# sch.net
KiCad netlist of a schematic drawn in Altium Designer
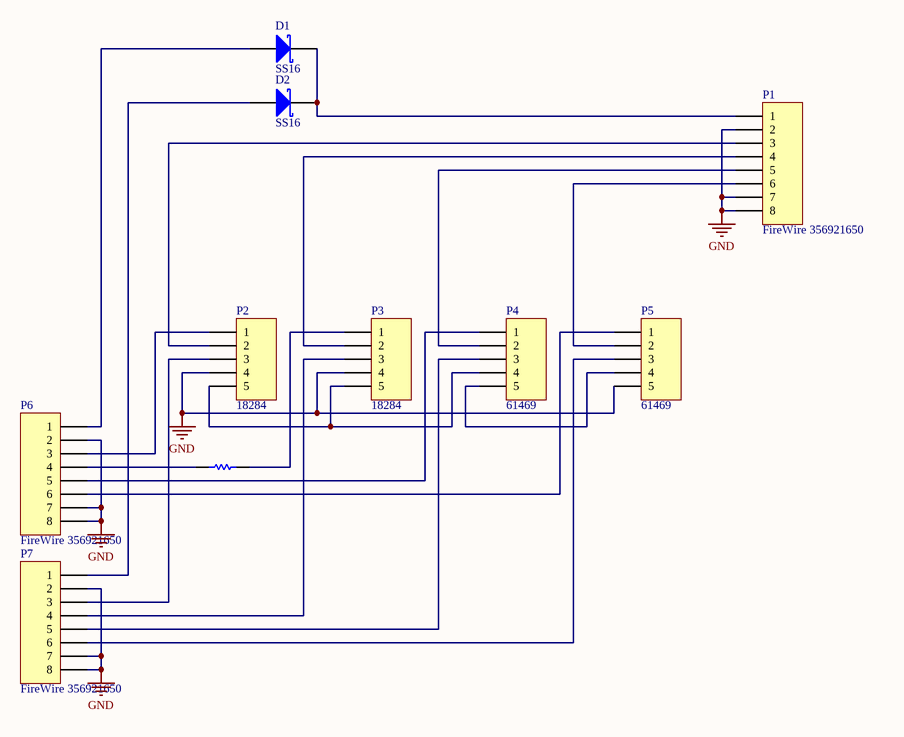
[diagram p0: sch.SchDoc]

(export (version "E")
  (design (tool "Eeschema 10.0.6"))
  (components
    (comp (ref "D1")
      (value "SS16")
      (footprint "RR_SMB")
      (description "DIODE SCHOTTKY 60V 1A SMA")
      (fields (field (name "MANUFACTURER") "FairchildSemiconductor"))
      (libsource (lib "RozumLibrary") (part "SS16"))
    )
    (comp (ref "D2")
      (value "SS16")
      (footprint "RR_SMB")
      (description "DIODE SCHOTTKY 60V 1A SMA")
      (fields (field (name "MANUFACTURER") "FairchildSemiconductor"))
      (libsource (lib "RozumLibrary") (part "SS16"))
    )
    (comp (ref "P1")
      (value "FireWire 356921650")
      (footprint "DS1102")
      (description "IEEE 1394 (DS1102), SMD розетка на плату (OBSOLETE)")
      (fields (field (name "PUBLISHER") "Altium Limited"))
      (libsource (lib "") (part "Header 8_1"))
    )
    (comp (ref "P2")
      (value "18284")
      (footprint "RES55A")
      (description "Header, 5-Pin")
      (fields (field (name "PUBLISHER") "Altium Limited"))
      (libsource (lib "Miscellaneous Connectors") (part "Header 5"))
    )
    (comp (ref "P3")
      (value "18284")
      (footprint "RES55A")
      (description "Header, 5-Pin")
      (fields (field (name "PUBLISHER") "Altium Limited"))
      (libsource (lib "Miscellaneous Connectors") (part "Header 5"))
    )
    (comp (ref "P4")
      (value "61469")
      (footprint "RES55A")
      (description "Header, 5-Pin")
      (fields (field (name "PUBLISHER") "Altium Limited"))
      (libsource (lib "Miscellaneous Connectors") (part "Header 5"))
    )
    (comp (ref "P5")
      (value "61469")
      (footprint "RES55A")
      (description "Header, 5-Pin")
      (fields (field (name "PUBLISHER") "Altium Limited"))
      (libsource (lib "Miscellaneous Connectors") (part "Header 5"))
    )
    (comp (ref "P6")
      (value "FireWire 356921650")
      (footprint "DS1102")
      (description "IEEE 1394 (DS1102), SMD розетка на плату (OBSOLETE)")
      (fields (field (name "PUBLISHER") "Altium Limited"))
      (libsource (lib "Miscellaneous Connectors") (part "Header 8"))
    )
    (comp (ref "P7")
      (value "FireWire 356921650")
      (footprint "DS1102")
      (description "IEEE 1394 (DS1102), SMD розетка на плату (OBSOLETE)")
      (fields (field (name "PUBLISHER") "Altium Limited"))
      (libsource (lib "Miscellaneous Connectors") (part "Header 8"))
    )
    (comp (ref "R1")
      (value "Res1")
      (footprint "0805")
      (description "Resistor")
      (fields (field (name "PUBLISHER") "Altium Limited"))
      (libsource (lib "Miscellaneous Devices") (part "Res1"))
    )
  )
  (nets
    (net (code "1") (name "GND") (class "Default")
      (node (ref "P1") (pin "2") (pinfunction "2_2") (pintype "passive"))
      (node (ref "P1") (pin "7") (pinfunction "7_7") (pintype "passive"))
      (node (ref "P1") (pin "8") (pinfunction "8_8") (pintype "passive"))
      (node (ref "P2") (pin "4") (pinfunction "4_4") (pintype "passive"))
      (node (ref "P3") (pin "4") (pinfunction "4_4") (pintype "passive"))
      (node (ref "P5") (pin "5") (pinfunction "5_5") (pintype "passive"))
      (node (ref "P6") (pin "2") (pinfunction "2_2") (pintype "passive"))
      (node (ref "P6") (pin "7") (pinfunction "7_7") (pintype "passive"))
      (node (ref "P6") (pin "8") (pinfunction "8_8") (pintype "passive"))
      (node (ref "P7") (pin "2") (pinfunction "2_2") (pintype "passive"))
      (node (ref "P7") (pin "7") (pinfunction "7_7") (pintype "passive"))
      (node (ref "P7") (pin "8") (pinfunction "8_8") (pintype "passive"))
    )
    (net (code "2") (name "Net-(D1-A)") (class "Default")
      (node (ref "D1") (pin "1") (pinfunction "A_1") (pintype "passive"))
      (node (ref "P6") (pin "1") (pinfunction "1_1") (pintype "passive"))
    )
    (net (code "3") (name "Net-(D1-K)") (class "Default")
      (node (ref "D1") (pin "2") (pinfunction "K_2") (pintype "passive"))
      (node (ref "D2") (pin "2") (pinfunction "K_2") (pintype "passive"))
      (node (ref "P1") (pin "1") (pinfunction "1_1") (pintype "passive"))
    )
    (net (code "4") (name "Net-(D2-A)") (class "Default")
      (node (ref "D2") (pin "1") (pinfunction "A_1") (pintype "passive"))
      (node (ref "P7") (pin "1") (pinfunction "1_1") (pintype "passive"))
    )
    (net (code "5") (name "Net-(P1-Pad3)") (class "Default")
      (node (ref "P1") (pin "3") (pinfunction "3_3") (pintype "passive"))
      (node (ref "P2") (pin "2") (pinfunction "2_2") (pintype "passive"))
    )
    (net (code "6") (name "Net-(P1-Pad4)") (class "Default")
      (node (ref "P1") (pin "4") (pinfunction "4_4") (pintype "passive"))
      (node (ref "P3") (pin "2") (pinfunction "2_2") (pintype "passive"))
    )
    (net (code "7") (name "Net-(P1-Pad5)") (class "Default")
      (node (ref "P1") (pin "5") (pinfunction "5_5") (pintype "passive"))
      (node (ref "P4") (pin "2") (pinfunction "2_2") (pintype "passive"))
    )
    (net (code "8") (name "Net-(P1-Pad6)") (class "Default")
      (node (ref "P1") (pin "6") (pinfunction "6_6") (pintype "passive"))
      (node (ref "P5") (pin "2") (pinfunction "2_2") (pintype "passive"))
    )
    (net (code "9") (name "Net-(P2-Pad1)") (class "Default")
      (node (ref "P2") (pin "1") (pinfunction "1_1") (pintype "passive"))
      (node (ref "P6") (pin "3") (pinfunction "3_3") (pintype "passive"))
    )
    (net (code "10") (name "Net-(P2-Pad3)") (class "Default")
      (node (ref "P2") (pin "3") (pinfunction "3_3") (pintype "passive"))
      (node (ref "P7") (pin "3") (pinfunction "3_3") (pintype "passive"))
    )
    (net (code "11") (name "Net-(P2-Pad5)") (class "Default")
      (node (ref "P2") (pin "5") (pinfunction "5_5") (pintype "passive"))
      (node (ref "P3") (pin "5") (pinfunction "5_5") (pintype "passive"))
      (node (ref "P4") (pin "4") (pinfunction "4_4") (pintype "passive"))
    )
    (net (code "12") (name "Net-(P3-Pad1)") (class "Default")
      (node (ref "P3") (pin "1") (pinfunction "1_1") (pintype "passive"))
      (node (ref "R1") (pin "2") (pinfunction "2_2") (pintype "passive"))
    )
    (net (code "13") (name "Net-(P3-Pad3)") (class "Default")
      (node (ref "P3") (pin "3") (pinfunction "3_3") (pintype "passive"))
      (node (ref "P7") (pin "4") (pinfunction "4_4") (pintype "passive"))
    )
    (net (code "14") (name "Net-(P4-Pad1)") (class "Default")
      (node (ref "P4") (pin "1") (pinfunction "1_1") (pintype "passive"))
      (node (ref "P6") (pin "5") (pinfunction "5_5") (pintype "passive"))
    )
    (net (code "15") (name "Net-(P4-Pad3)") (class "Default")
      (node (ref "P4") (pin "3") (pinfunction "3_3") (pintype "passive"))
      (node (ref "P7") (pin "5") (pinfunction "5_5") (pintype "passive"))
    )
    (net (code "16") (name "Net-(P4-Pad5)") (class "Default")
      (node (ref "P4") (pin "5") (pinfunction "5_5") (pintype "passive"))
      (node (ref "P5") (pin "4") (pinfunction "4_4") (pintype "passive"))
    )
    (net (code "17") (name "Net-(P5-Pad1)") (class "Default")
      (node (ref "P5") (pin "1") (pinfunction "1_1") (pintype "passive"))
      (node (ref "P6") (pin "6") (pinfunction "6_6") (pintype "passive"))
    )
    (net (code "18") (name "Net-(P5-Pad3)") (class "Default")
      (node (ref "P5") (pin "3") (pinfunction "3_3") (pintype "passive"))
      (node (ref "P7") (pin "6") (pinfunction "6_6") (pintype "passive"))
    )
    (net (code "19") (name "Net-(P6-Pad4)") (class "Default")
      (node (ref "P6") (pin "4") (pinfunction "4_4") (pintype "passive"))
      (node (ref "R1") (pin "1") (pinfunction "1_1") (pintype "passive"))
    )
  )
)
